# SELE_PROJECT.net
KiCad netlist of a schematic drawn in EAGLE
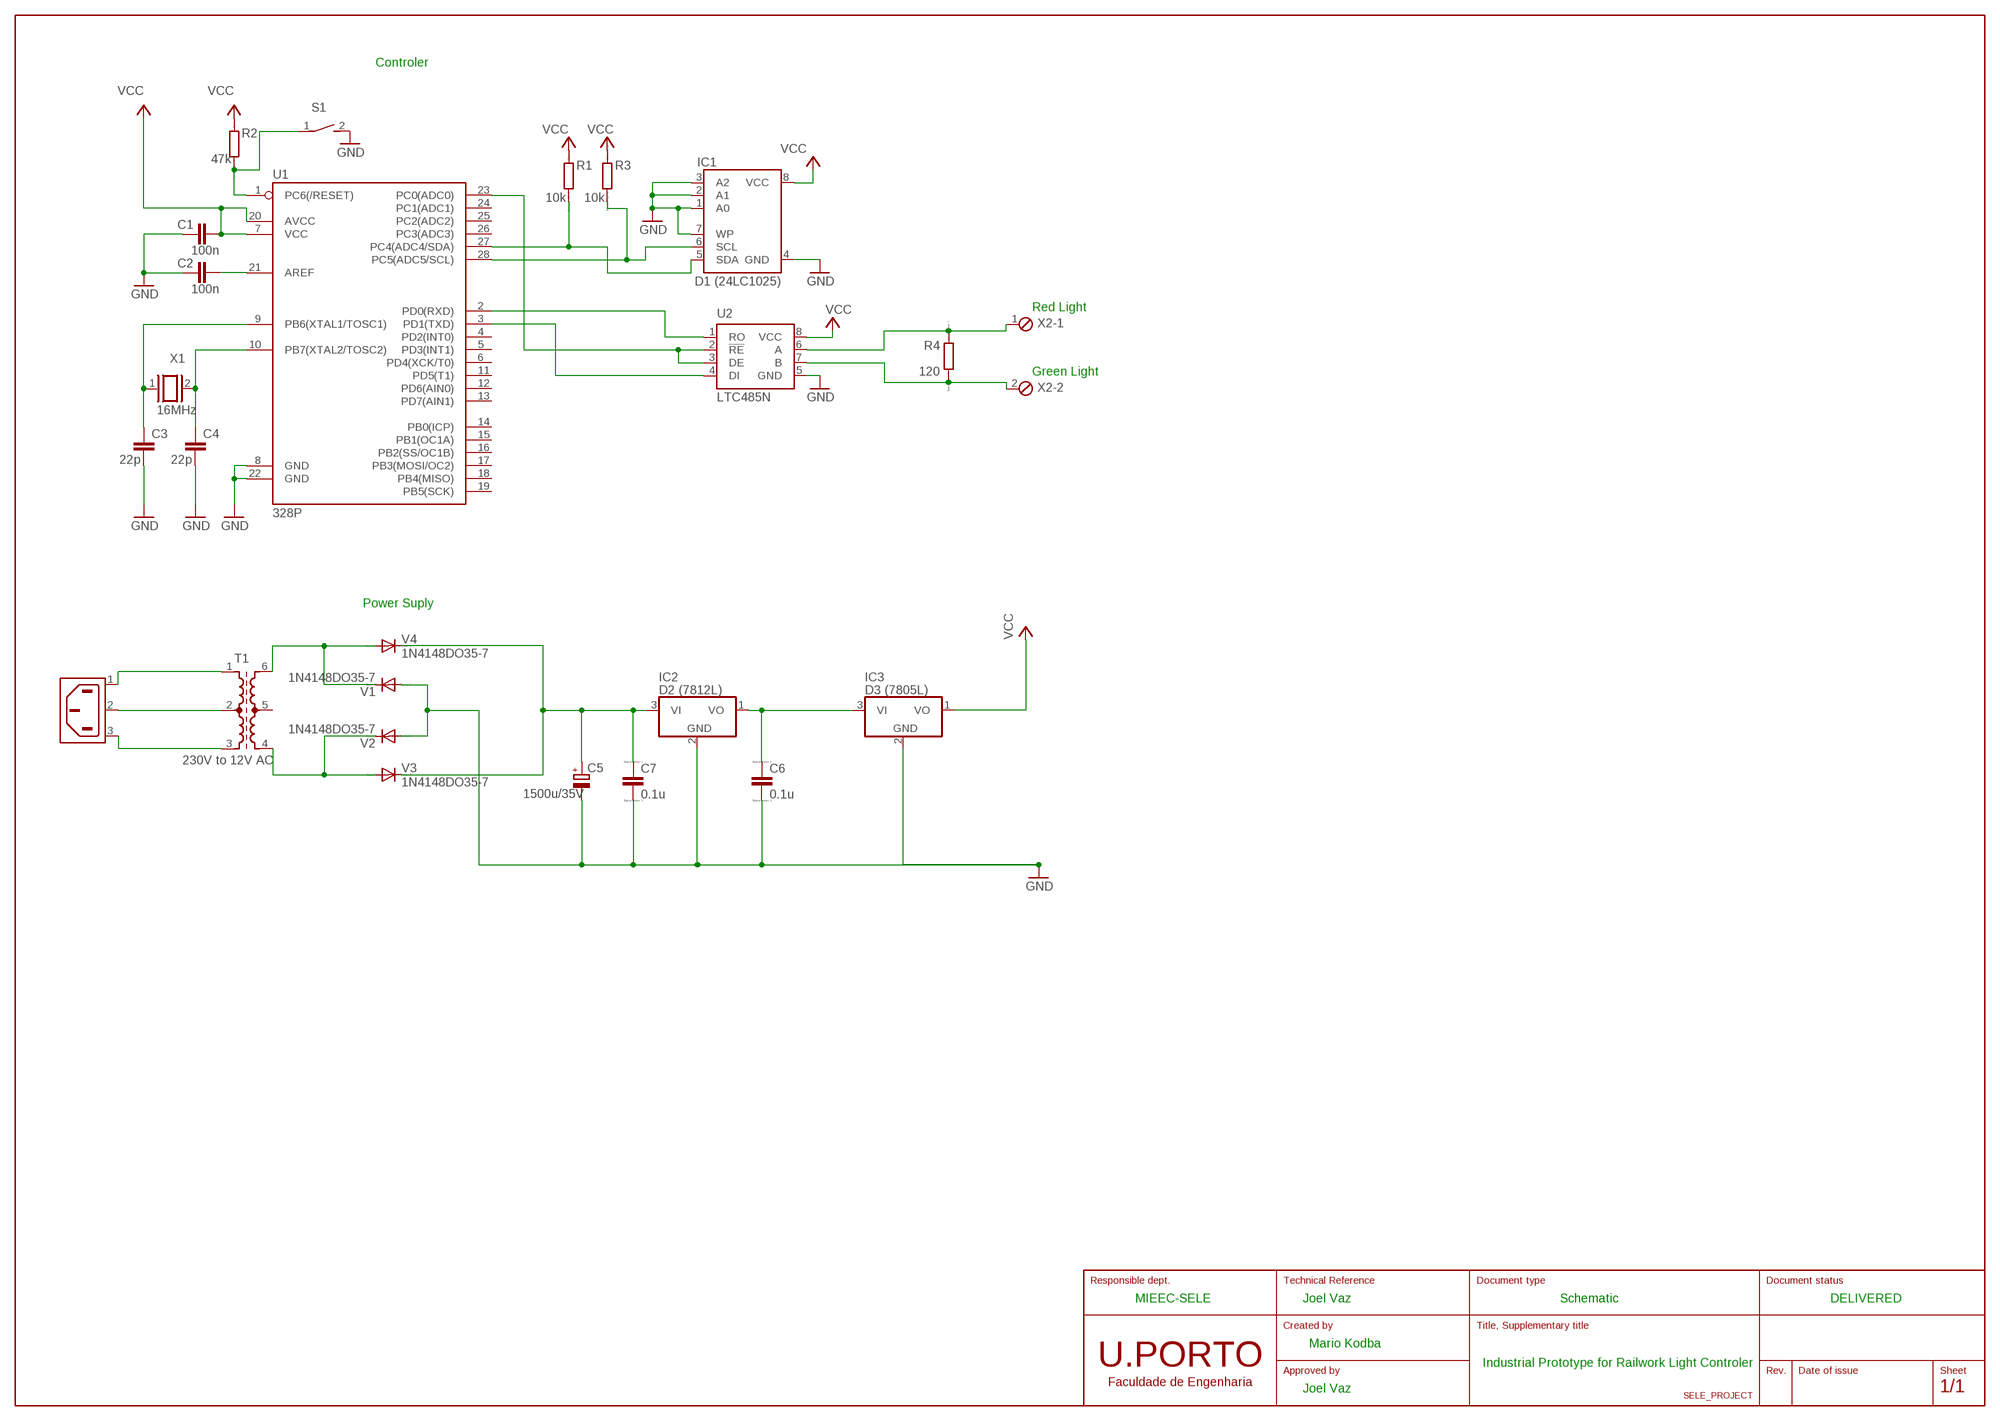
[diagram p0: schematic, sheet 1]

(export (version "E")
  (design (tool "Eeschema 10.0.6"))
  (components
    (comp (ref "C1")
      (value "100n")
      (footprint "eagle-import:C2.5-3")
      (libsource (lib "eagle-import") (part "C2,5-3"))
    )
    (comp (ref "C2")
      (value "100n")
      (footprint "eagle-import:C2.5-3")
      (libsource (lib "eagle-import") (part "C2,5-3"))
    )
    (comp (ref "C3")
      (value "22p")
      (footprint "eagle-import:C2.5-3")
      (libsource (lib "eagle-import") (part "C2,5-3"))
    )
    (comp (ref "C4")
      (value "22p")
      (footprint "eagle-import:C2.5-3")
      (libsource (lib "eagle-import") (part "C2,5-3"))
    )
    (comp (ref "C5")
      (value "1500u/35V")
      (footprint "eagle-import:150CLZ-1010")
      (libsource (lib "eagle-import") (part "CPOL-EU150CLZ-1010"))
    )
    (comp (ref "C6")
      (value "0.1u")
      (footprint "eagle-import:C1210")
      (libsource (lib "eagle-import") (part "CC1210"))
    )
    (comp (ref "C7")
      (value "0.1u")
      (footprint "eagle-import:C1210")
      (libsource (lib "eagle-import") (part "CC1210"))
    )
    (comp (ref "IC1")
      (value "D1 (24LC1025)")
      (footprint "eagle-import:DIL08")
      (fields (field (name "MPN") "AT24C1024BW-SH-B"))
      (libsource (lib "eagle-import") (part "AT24CP"))
    )
    (comp (ref "IC2")
      (value "D2 (7812L)")
      (footprint "eagle-import:TO92")
      (libsource (lib "eagle-import") (part "78L12"))
    )
    (comp (ref "IC3")
      (value "D3 (7805L)")
      (footprint "eagle-import:TO92")
      (libsource (lib "eagle-import") (part "78L05"))
    )
    (comp (ref "R1")
      (value "10k")
      (footprint "eagle-import:R0805")
      (libsource (lib "eagle-import") (part "R"))
    )
    (comp (ref "R2")
      (value "47k")
      (footprint "eagle-import:R0805")
      (libsource (lib "eagle-import") (part "R"))
    )
    (comp (ref "R3")
      (value "10k")
      (footprint "eagle-import:R0805")
      (libsource (lib "eagle-import") (part "R"))
    )
    (comp (ref "R4")
      (value "120")
      (footprint "eagle-import:R0805")
      (libsource (lib "eagle-import") (part "R"))
    )
    (comp (ref "S1")
      (value "DS01E")
      (footprint "eagle-import:DS-01")
      (libsource (lib "eagle-import") (part "DS01E"))
    )
    (comp (ref "T1")
      (value "230V to 12V AC")
      (footprint "eagle-import:SM-EP7")
      (libsource (lib "eagle-import") (part "SM-EP7"))
    )
    (comp (ref "U1")
      (value "328P")
      (footprint "eagle-import:MICROCONTROLLER_DIP28")
      (libsource (lib "eagle-import") (part "ATMEGA328P-PDIP"))
    )
    (comp (ref "U2")
      (value "LTC485N")
      (footprint "eagle-import:DIL08")
      (libsource (lib "eagle-import") (part "LTC485N"))
    )
    (comp (ref "V1")
      (value "1N4148DO35-7")
      (footprint "eagle-import:DO35-7")
      (libsource (lib "eagle-import") (part "1N4148DO35-7"))
    )
    (comp (ref "V2")
      (value "1N4148DO35-7")
      (footprint "eagle-import:DO35-7")
      (libsource (lib "eagle-import") (part "1N4148DO35-7"))
    )
    (comp (ref "V3")
      (value "1N4148DO35-7")
      (footprint "eagle-import:DO35-7")
      (libsource (lib "eagle-import") (part "1N4148DO35-7"))
    )
    (comp (ref "V4")
      (value "1N4148DO35-7")
      (footprint "eagle-import:DO35-7")
      (libsource (lib "eagle-import") (part "1N4148DO35-7"))
    )
    (comp (ref "X1")
      (value "16MHz")
      (footprint "eagle-import:Q")
      (libsource (lib "eagle-import") (part "XTAL"))
    )
    (comp (ref "X2")
      (value "MPT2")
      (footprint "eagle-import:2POL254")
      (libsource (lib "eagle-import") (part "MPT2"))
    )
    (comp (ref "X4")
      (value "6ESRM-P")
      (footprint "eagle-import:6ESRM-P")
      (fields (field (name "MF") "TYCO ELECTRONICS"))
      (libsource (lib "eagle-import") (part "6ESRM-P"))
    )
  )
  (nets
    (net (code "1") (name "GND") (class "Default")
      (node (ref "C1") (pin "1") (pinfunction "1_1") (pintype "passive"))
      (node (ref "C2") (pin "1") (pinfunction "1_1") (pintype "passive"))
      (node (ref "C3") (pin "2") (pinfunction "2_2") (pintype "passive"))
      (node (ref "C4") (pin "2") (pinfunction "2_2") (pintype "passive"))
      (node (ref "C5") (pin "-") (pinfunction "-_-") (pintype "passive"))
      (node (ref "C6") (pin "2") (pinfunction "2_2") (pintype "passive"))
      (node (ref "C7") (pin "2") (pinfunction "2_2") (pintype "passive"))
      (node (ref "IC1") (pin "1") (pinfunction "A0_1") (pintype "input"))
      (node (ref "IC1") (pin "2") (pinfunction "A1_2") (pintype "input"))
      (node (ref "IC1") (pin "3") (pinfunction "A2_3") (pintype "input"))
      (node (ref "IC1") (pin "4") (pinfunction "GND_4") (pintype "power_in"))
      (node (ref "IC1") (pin "7") (pinfunction "WP_7") (pintype "input"))
      (node (ref "IC2") (pin "2") (pinfunction "GND_2") (pintype "passive"))
      (node (ref "IC3") (pin "2") (pinfunction "GND_2") (pintype "passive"))
      (node (ref "S1") (pin "2") (pinfunction "2_2") (pintype "passive"))
      (node (ref "U1") (pin "22") (pinfunction "GND_22") (pintype "bidirectional"))
      (node (ref "U1") (pin "8") (pinfunction "GND_8") (pintype "bidirectional"))
      (node (ref "U2") (pin "5") (pinfunction "GND_5") (pintype "input"))
      (node (ref "V1") (pin "A") (pinfunction "A_A") (pintype "passive"))
      (node (ref "V2") (pin "A") (pinfunction "A_A") (pintype "passive"))
    )
    (net (code "2") (name "Net-(IC1-SCL)") (class "Default")
      (node (ref "IC1") (pin "6") (pinfunction "SCL_6") (pintype "bidirectional"))
      (node (ref "R3") (pin "2") (pinfunction "2_2") (pintype "passive"))
      (node (ref "U1") (pin "28") (pinfunction "PC5(ADC5/SCL)_28") (pintype "bidirectional"))
    )
    (net (code "3") (name "Net-(IC1-SDA)") (class "Default")
      (node (ref "IC1") (pin "5") (pinfunction "SDA_5") (pintype "bidirectional"))
      (node (ref "R1") (pin "2") (pinfunction "2_2") (pintype "passive"))
      (node (ref "U1") (pin "27") (pinfunction "PC4(ADC4/SDA)_27") (pintype "bidirectional"))
    )
    (net (code "4") (name "Net-(IC2-VI)") (class "Default")
      (node (ref "C5") (pin "+") (pinfunction "+_+") (pintype "passive"))
      (node (ref "C7") (pin "1") (pinfunction "1_1") (pintype "passive"))
      (node (ref "IC2") (pin "3") (pinfunction "VI_3") (pintype "input"))
      (node (ref "V3") (pin "C") (pinfunction "C_C") (pintype "passive"))
      (node (ref "V4") (pin "C") (pinfunction "C_C") (pintype "passive"))
    )
    (net (code "5") (name "Net-(IC2-VO)") (class "Default")
      (node (ref "C6") (pin "1") (pinfunction "1_1") (pintype "passive"))
      (node (ref "IC2") (pin "1") (pinfunction "VO_1") (pintype "passive"))
      (node (ref "IC3") (pin "3") (pinfunction "VI_3") (pintype "input"))
    )
    (net (code "6") (name "Net-(T1-Pad4)") (class "Default")
      (node (ref "T1") (pin "4") (pinfunction "4_4") (pintype "passive"))
      (node (ref "V2") (pin "C") (pinfunction "C_C") (pintype "passive"))
      (node (ref "V3") (pin "A") (pinfunction "A_A") (pintype "passive"))
    )
    (net (code "7") (name "Net-(T1-Pad6)") (class "Default")
      (node (ref "T1") (pin "6") (pinfunction "6_6") (pintype "passive"))
      (node (ref "V1") (pin "C") (pinfunction "C_C") (pintype "passive"))
      (node (ref "V4") (pin "A") (pinfunction "A_A") (pintype "passive"))
    )
    (net (code "8") (name "Net-(U1-AREF)") (class "Default")
      (node (ref "C2") (pin "2") (pinfunction "2_2") (pintype "passive"))
      (node (ref "U1") (pin "21") (pinfunction "AREF_21") (pintype "bidirectional"))
    )
    (net (code "9") (name "Net-(U1-PB6(XTAL1{slash}TOSC1))") (class "Default")
      (node (ref "C3") (pin "1") (pinfunction "1_1") (pintype "passive"))
      (node (ref "U1") (pin "9") (pinfunction "PB6(XTAL1/TOSC1)_9") (pintype "bidirectional"))
      (node (ref "X1") (pin "1") (pinfunction "1_1") (pintype "passive"))
    )
    (net (code "10") (name "Net-(U1-PB7(XTAL2{slash}TOSC2))") (class "Default")
      (node (ref "C4") (pin "1") (pinfunction "1_1") (pintype "passive"))
      (node (ref "U1") (pin "10") (pinfunction "PB7(XTAL2/TOSC2)_10") (pintype "bidirectional"))
      (node (ref "X1") (pin "2") (pinfunction "2_2") (pintype "passive"))
    )
    (net (code "11") (name "Net-(U1-PC0(ADC0))") (class "Default")
      (node (ref "U1") (pin "23") (pinfunction "PC0(ADC0)_23") (pintype "bidirectional"))
      (node (ref "U2") (pin "2") (pinfunction "~{RE}_2") (pintype "input"))
      (node (ref "U2") (pin "3") (pinfunction "DE_3") (pintype "input"))
    )
    (net (code "12") (name "Net-(U1-PC6({slash}RESET))") (class "Default")
      (node (ref "R2") (pin "2") (pinfunction "2_2") (pintype "passive"))
      (node (ref "S1") (pin "1") (pinfunction "1_1") (pintype "passive"))
      (node (ref "U1") (pin "1") (pinfunction "PC6(/RESET)_1") (pintype "bidirectional"))
    )
    (net (code "13") (name "Net-(U1-PD0(RXD))") (class "Default")
      (node (ref "U1") (pin "2") (pinfunction "PD0(RXD)_2") (pintype "bidirectional"))
      (node (ref "U2") (pin "1") (pinfunction "RO_1") (pintype "output"))
    )
    (net (code "14") (name "Net-(U1-PD1(TXD))") (class "Default")
      (node (ref "U1") (pin "3") (pinfunction "PD1(TXD)_3") (pintype "bidirectional"))
      (node (ref "U2") (pin "4") (pinfunction "DI_4") (pintype "input"))
    )
    (net (code "15") (name "Net-(U2-A)") (class "Default")
      (node (ref "R4") (pin "1") (pinfunction "1_1") (pintype "passive"))
      (node (ref "U2") (pin "6") (pinfunction "A_6") (pintype "bidirectional"))
      (node (ref "X2") (pin "1") (pinfunction "1_1") (pintype "passive"))
    )
    (net (code "16") (name "Net-(U2-B)") (class "Default")
      (node (ref "R4") (pin "2") (pinfunction "2_2") (pintype "passive"))
      (node (ref "U2") (pin "7") (pinfunction "B_7") (pintype "bidirectional"))
      (node (ref "X2") (pin "2") (pinfunction "1_2") (pintype "passive"))
    )
    (net (code "17") (name "Net-(X4-AC1)") (class "Default")
      (node (ref "T1") (pin "1") (pinfunction "1_1") (pintype "passive"))
      (node (ref "X4") (pin "1") (pinfunction "AC1_1") (pintype "passive"))
    )
    (net (code "18") (name "Net-(X4-AC2)") (class "Default")
      (node (ref "T1") (pin "3") (pinfunction "3_3") (pintype "passive"))
      (node (ref "X4") (pin "3") (pinfunction "AC2_3") (pintype "passive"))
    )
    (net (code "19") (name "Net-(X4-SH)") (class "Default")
      (node (ref "T1") (pin "2") (pinfunction "2_2") (pintype "passive"))
      (node (ref "X4") (pin "2") (pinfunction "SH_2") (pintype "passive"))
    )
    (net (code "20") (name "VCC") (class "Default")
      (node (ref "C1") (pin "2") (pinfunction "2_2") (pintype "passive"))
      (node (ref "IC1") (pin "8") (pinfunction "VCC_8") (pintype "power_in"))
      (node (ref "IC3") (pin "1") (pinfunction "VO_1") (pintype "passive"))
      (node (ref "R1") (pin "1") (pinfunction "1_1") (pintype "passive"))
      (node (ref "R2") (pin "1") (pinfunction "1_1") (pintype "passive"))
      (node (ref "R3") (pin "1") (pinfunction "1_1") (pintype "passive"))
      (node (ref "U1") (pin "20") (pinfunction "AVCC_20") (pintype "bidirectional"))
      (node (ref "U1") (pin "7") (pinfunction "VCC_7") (pintype "bidirectional"))
      (node (ref "U2") (pin "8") (pinfunction "VCC_8") (pintype "input"))
    )
    (net (code "21") (name "unconnected-(T1-Pad5)") (class "Default")
      (node (ref "T1") (pin "5") (pinfunction "5_5") (pintype "passive"))
    )
    (net (code "22") (name "unconnected-(U1-PB0(ICP)-Pad14)") (class "Default")
      (node (ref "U1") (pin "14") (pinfunction "PB0(ICP)_14") (pintype "bidirectional"))
    )
    (net (code "23") (name "unconnected-(U1-PB1(OC1A)-Pad15)") (class "Default")
      (node (ref "U1") (pin "15") (pinfunction "PB1(OC1A)_15") (pintype "bidirectional"))
    )
    (net (code "24") (name "unconnected-(U1-PB2(SS{slash}OC1B)-Pad16)") (class "Default")
      (node (ref "U1") (pin "16") (pinfunction "PB2(SS/OC1B)_16") (pintype "bidirectional"))
    )
    (net (code "25") (name "unconnected-(U1-PB3(MOSI{slash}OC2)-Pad17)") (class "Default")
      (node (ref "U1") (pin "17") (pinfunction "PB3(MOSI/OC2)_17") (pintype "bidirectional"))
    )
    (net (code "26") (name "unconnected-(U1-PB4(MISO)-Pad18)") (class "Default")
      (node (ref "U1") (pin "18") (pinfunction "PB4(MISO)_18") (pintype "bidirectional"))
    )
    (net (code "27") (name "unconnected-(U1-PB5(SCK)-Pad19)") (class "Default")
      (node (ref "U1") (pin "19") (pinfunction "PB5(SCK)_19") (pintype "bidirectional"))
    )
    (net (code "28") (name "unconnected-(U1-PC1(ADC1)-Pad24)") (class "Default")
      (node (ref "U1") (pin "24") (pinfunction "PC1(ADC1)_24") (pintype "bidirectional"))
    )
    (net (code "29") (name "unconnected-(U1-PC2(ADC2)-Pad25)") (class "Default")
      (node (ref "U1") (pin "25") (pinfunction "PC2(ADC2)_25") (pintype "bidirectional"))
    )
    (net (code "30") (name "unconnected-(U1-PC3(ADC3)-Pad26)") (class "Default")
      (node (ref "U1") (pin "26") (pinfunction "PC3(ADC3)_26") (pintype "bidirectional"))
    )
    (net (code "31") (name "unconnected-(U1-PD2(INT0)-Pad4)") (class "Default")
      (node (ref "U1") (pin "4") (pinfunction "PD2(INT0)_4") (pintype "bidirectional"))
    )
    (net (code "32") (name "unconnected-(U1-PD3(INT1)-Pad5)") (class "Default")
      (node (ref "U1") (pin "5") (pinfunction "PD3(INT1)_5") (pintype "bidirectional"))
    )
    (net (code "33") (name "unconnected-(U1-PD4(XCK{slash}T0)-Pad6)") (class "Default")
      (node (ref "U1") (pin "6") (pinfunction "PD4(XCK/T0)_6") (pintype "bidirectional"))
    )
    (net (code "34") (name "unconnected-(U1-PD5(T1)-Pad11)") (class "Default")
      (node (ref "U1") (pin "11") (pinfunction "PD5(T1)_11") (pintype "bidirectional"))
    )
    (net (code "35") (name "unconnected-(U1-PD6(AIN0)-Pad12)") (class "Default")
      (node (ref "U1") (pin "12") (pinfunction "PD6(AIN0)_12") (pintype "bidirectional"))
    )
    (net (code "36") (name "unconnected-(U1-PD7(AIN1)-Pad13)") (class "Default")
      (node (ref "U1") (pin "13") (pinfunction "PD7(AIN1)_13") (pintype "bidirectional"))
    )
  )
)
